# rgbstripe_msgeq7_pcb.net
KiCad netlist of a schematic drawn in EAGLE
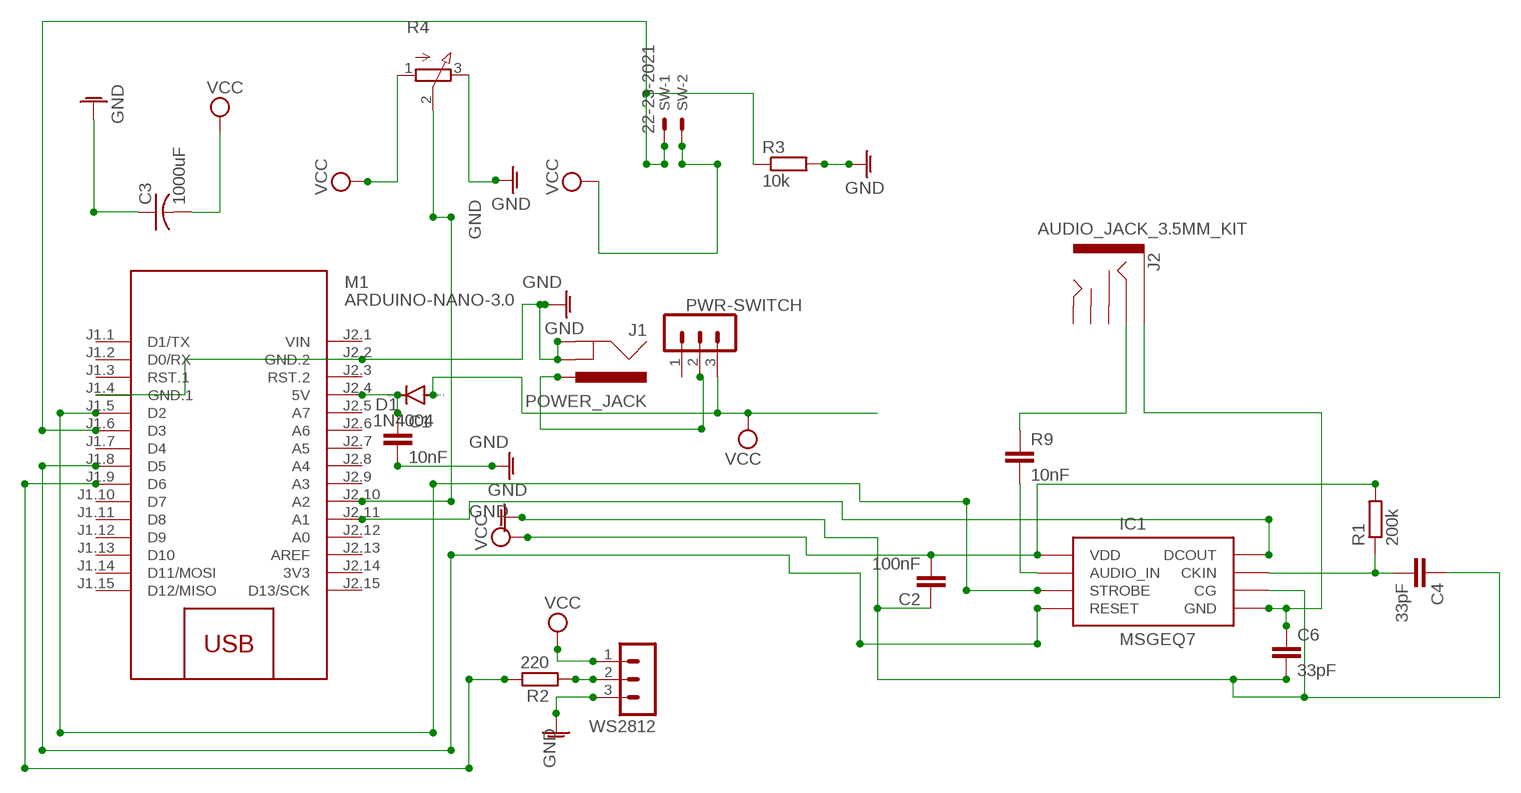
[diagram p0: schematic, sheet 1]

(export (version "E")
  (design (tool "Eeschema 10.0.6"))
  (components
    (comp (ref "C1")
      (value "10nF")
      (footprint "eagle-import:C025-025X050")
      (libsource (lib "eagle-import") (part "C-EU025-025X050"))
    )
    (comp (ref "C2")
      (value "100nF")
      (footprint "eagle-import:C025-025X050")
      (libsource (lib "eagle-import") (part "C-EU025-025X050"))
    )
    (comp (ref "C3")
      (value "1000uF")
      (footprint "eagle-import:C050-024X044")
      (libsource (lib "eagle-import") (part "C-US050-024X044"))
    )
    (comp (ref "C4")
      (value "33pF")
      (footprint "eagle-import:C025-025X050")
      (libsource (lib "eagle-import") (part "C-EU025-025X050"))
    )
    (comp (ref "C6")
      (value "33pF")
      (footprint "eagle-import:C025-025X050")
      (libsource (lib "eagle-import") (part "C-EU025-025X050"))
    )
    (comp (ref "D1")
      (value "1N4004")
      (footprint "eagle-import:DO41-10")
      (libsource (lib "eagle-import") (part "1N4004"))
    )
    (comp (ref "IC1")
      (value "MSGEQ7P")
      (footprint "eagle-import:DIP08")
      (libsource (lib "eagle-import") (part "MSGEQ7DIL"))
    )
    (comp (ref "J1")
      (value "POWER_JACK")
      (footprint "eagle-import:POWER_JACK_PTH")
      (libsource (lib "eagle-import") (part "POWER_JACK"))
    )
    (comp (ref "J2")
      (value "AUDIO_JACK_3.5MM_KIT")
      (footprint "eagle-import:AUDIO-JACK-KIT")
      (libsource (lib "eagle-import") (part "AUDIO_JACK_3.5MM_KIT"))
    )
    (comp (ref "M1")
      (value "ARDUINO-NANO-3.0")
      (footprint "eagle-import:ARDUINO-NANO-3.0")
      (libsource (lib "eagle-import") (part "ARDUINO-NANO-3.0"))
    )
    (comp (ref "PWR-SWITCH")
      (value "MA03-1")
      (footprint "eagle-import:MA03-1")
      (libsource (lib "eagle-import") (part "MA03-1"))
    )
    (comp (ref "R1")
      (value "200k")
      (footprint "eagle-import:0204_5")
      (libsource (lib "eagle-import") (part "R-EU_0204/5"))
    )
    (comp (ref "R2")
      (value "220")
      (footprint "eagle-import:0204_5")
      (libsource (lib "eagle-import") (part "R-EU_0204/5"))
    )
    (comp (ref "R3")
      (value "10k")
      (footprint "eagle-import:0204_5")
      (libsource (lib "eagle-import") (part "R-EU_0204/5"))
    )
    (comp (ref "R4")
      (value "3RP/1610N")
      (footprint "eagle-import:3RP_1610N")
      (libsource (lib "eagle-import") (part "3RP/1610N"))
    )
    (comp (ref "R9")
      (value "10nF")
      (footprint "eagle-import:C025-025X050")
      (libsource (lib "eagle-import") (part "C-EU025-025X050"))
    )
    (comp (ref "SW")
      (value "22-23-2021")
      (footprint "eagle-import:22-23-2021")
      (fields (field (name "MF") "MOLEX"))
      (libsource (lib "eagle-import") (part "22-23-2021"))
    )
    (comp (ref "WS2812")
      (value "MA03-1")
      (footprint "eagle-import:MA03-1")
      (libsource (lib "eagle-import") (part "MA03-1"))
    )
  )
  (nets
    (net (code "1") (name "/3V3") (class "Default")
      (node (ref "M1") (pin "J2.14") (pinfunction "3V3_J2.14") (pintype "power_in"))
    )
    (net (code "2") (name "/VIN") (class "Default")
      (node (ref "M1") (pin "J2.1") (pinfunction "VIN_J2.1") (pintype "power_in"))
    )
    (net (code "3") (name "GND") (class "Default")
      (node (ref "C1") (pin "2") (pinfunction "2_2") (pintype "passive"))
      (node (ref "C2") (pin "1") (pinfunction "1_1") (pintype "passive"))
      (node (ref "C3") (pin "1") (pinfunction "1_1") (pintype "passive"))
      (node (ref "C4") (pin "1") (pinfunction "1_1") (pintype "passive"))
      (node (ref "C6") (pin "2") (pinfunction "2_2") (pintype "passive"))
      (node (ref "IC1") (pin "6") (pinfunction "CG_6") (pintype "bidirectional"))
      (node (ref "J1") (pin "GND") (pinfunction "GND_GND") (pintype "bidirectional"))
      (node (ref "J1") (pin "GNDBREAK") (pinfunction "GNDBREAK_GNDBREAK") (pintype "bidirectional"))
      (node (ref "M1") (pin "J1.4") (pinfunction "GND.1_J1.4") (pintype "power_in"))
      (node (ref "M1") (pin "J2.2") (pinfunction "GND.2_J2.2") (pintype "power_in"))
      (node (ref "R3") (pin "2") (pinfunction "2_2") (pintype "passive"))
      (node (ref "R4") (pin "3") (pinfunction "E_3") (pintype "passive"))
      (node (ref "WS2812") (pin "3") (pinfunction "3_3") (pintype "passive"))
    )
    (net (code "4") (name "Net-(IC1-AUDIO_IN)") (class "Default")
      (node (ref "IC1") (pin "5") (pinfunction "AUDIO_IN_5") (pintype "input"))
      (node (ref "R9") (pin "2") (pinfunction "2_2") (pintype "passive"))
    )
    (net (code "5") (name "Net-(IC1-CKIN)") (class "Default")
      (node (ref "C4") (pin "2") (pinfunction "2_2") (pintype "passive"))
      (node (ref "IC1") (pin "8") (pinfunction "CKIN_8") (pintype "bidirectional"))
      (node (ref "R1") (pin "1") (pinfunction "1_1") (pintype "passive"))
    )
    (net (code "6") (name "Net-(IC1-DCOUT)") (class "Default")
      (node (ref "IC1") (pin "3") (pinfunction "DCOUT_3") (pintype "bidirectional"))
      (node (ref "M1") (pin "J2.11") (pinfunction "A1_J2.11") (pintype "bidirectional"))
    )
    (net (code "7") (name "Net-(IC1-GND)") (class "Default")
      (node (ref "C6") (pin "1") (pinfunction "1_1") (pintype "passive"))
      (node (ref "IC1") (pin "2") (pinfunction "GND_2") (pintype "bidirectional"))
      (node (ref "J2") (pin "SLEEVE") (pinfunction "SLEEVE_SLEEVE") (pintype "bidirectional"))
    )
    (net (code "8") (name "Net-(IC1-RESET)") (class "Default")
      (node (ref "IC1") (pin "7") (pinfunction "RESET_7") (pintype "input"))
      (node (ref "M1") (pin "J1.8") (pinfunction "D5_J1.8") (pintype "bidirectional"))
    )
    (net (code "9") (name "Net-(IC1-STROBE)") (class "Default")
      (node (ref "IC1") (pin "4") (pinfunction "STROBE_4") (pintype "input"))
      (node (ref "M1") (pin "J1.5") (pinfunction "D2_J1.5") (pintype "bidirectional"))
    )
    (net (code "10") (name "Net-(J1-PadPWR)") (class "Default")
      (node (ref "J1") (pin "PWR") (pinfunction "PWR_PWR") (pintype "bidirectional"))
      (node (ref "PWR-SWITCH") (pin "2") (pinfunction "2_2") (pintype "passive"))
    )
    (net (code "11") (name "Net-(J2-PadRING)") (class "Default")
      (node (ref "J2") (pin "RING") (pinfunction "RING_RING") (pintype "bidirectional"))
      (node (ref "R9") (pin "1") (pinfunction "1_1") (pintype "passive"))
    )
    (net (code "12") (name "Net-(M1-5V)") (class "Default")
      (node (ref "C1") (pin "1") (pinfunction "1_1") (pintype "passive"))
      (node (ref "D1") (pin "C") (pinfunction "C_C") (pintype "passive"))
      (node (ref "M1") (pin "J2.4") (pinfunction "5V_J2.4") (pintype "power_in"))
    )
    (net (code "13") (name "Net-(M1-A2)") (class "Default")
      (node (ref "M1") (pin "J2.10") (pinfunction "A2_J2.10") (pintype "bidirectional"))
      (node (ref "R4") (pin "2") (pinfunction "S_2") (pintype "passive"))
    )
    (net (code "14") (name "Net-(M1-D3)") (class "Default")
      (node (ref "M1") (pin "J1.6") (pinfunction "D3_J1.6") (pintype "bidirectional"))
      (node (ref "R3") (pin "1") (pinfunction "1_1") (pintype "passive"))
      (node (ref "SW") (pin "1") (pinfunction "S_1") (pintype "passive"))
    )
    (net (code "15") (name "Net-(M1-D6)") (class "Default")
      (node (ref "M1") (pin "J1.9") (pinfunction "D6_J1.9") (pintype "bidirectional"))
      (node (ref "R2") (pin "2") (pinfunction "2_2") (pintype "passive"))
    )
    (net (code "16") (name "Net-(R2-Pad1)") (class "Default")
      (node (ref "R2") (pin "1") (pinfunction "1_1") (pintype "passive"))
      (node (ref "WS2812") (pin "2") (pinfunction "2_2") (pintype "passive"))
    )
    (net (code "17") (name "VCC") (class "Default")
      (node (ref "C2") (pin "2") (pinfunction "2_2") (pintype "passive"))
      (node (ref "C3") (pin "2") (pinfunction "2_2") (pintype "passive"))
      (node (ref "D1") (pin "A") (pinfunction "A_A") (pintype "passive"))
      (node (ref "IC1") (pin "1") (pinfunction "VDD_1") (pintype "input"))
      (node (ref "PWR-SWITCH") (pin "3") (pinfunction "3_3") (pintype "passive"))
      (node (ref "R1") (pin "2") (pinfunction "2_2") (pintype "passive"))
      (node (ref "R4") (pin "1") (pinfunction "A_1") (pintype "passive"))
      (node (ref "SW") (pin "2") (pinfunction "S_2") (pintype "passive"))
      (node (ref "WS2812") (pin "1") (pinfunction "1_1") (pintype "passive"))
    )
    (net (code "18") (name "unconnected-(J2-PadRSH)") (class "Default")
      (node (ref "J2") (pin "RSH") (pinfunction "RSH_RSH") (pintype "bidirectional"))
    )
    (net (code "19") (name "unconnected-(J2-PadTIP)") (class "Default")
      (node (ref "J2") (pin "TIP") (pinfunction "TIP_TIP") (pintype "bidirectional"))
    )
    (net (code "20") (name "unconnected-(J2-PadTSH)") (class "Default")
      (node (ref "J2") (pin "TSH") (pinfunction "TSH_TSH") (pintype "bidirectional"))
    )
    (net (code "21") (name "unconnected-(M1-A0-PadJ2.12)") (class "Default")
      (node (ref "M1") (pin "J2.12") (pinfunction "A0_J2.12") (pintype "bidirectional"))
    )
    (net (code "22") (name "unconnected-(M1-A3-PadJ2.9)") (class "Default")
      (node (ref "M1") (pin "J2.9") (pinfunction "A3_J2.9") (pintype "bidirectional"))
    )
    (net (code "23") (name "unconnected-(M1-A4-PadJ2.8)") (class "Default")
      (node (ref "M1") (pin "J2.8") (pinfunction "A4_J2.8") (pintype "bidirectional"))
    )
    (net (code "24") (name "unconnected-(M1-A5-PadJ2.7)") (class "Default")
      (node (ref "M1") (pin "J2.7") (pinfunction "A5_J2.7") (pintype "bidirectional"))
    )
    (net (code "25") (name "unconnected-(M1-A6-PadJ2.6)") (class "Default")
      (node (ref "M1") (pin "J2.6") (pinfunction "A6_J2.6") (pintype "bidirectional"))
    )
    (net (code "26") (name "unconnected-(M1-A7-PadJ2.5)") (class "Default")
      (node (ref "M1") (pin "J2.5") (pinfunction "A7_J2.5") (pintype "bidirectional"))
    )
    (net (code "27") (name "unconnected-(M1-AREF-PadJ2.13)") (class "Default")
      (node (ref "M1") (pin "J2.13") (pinfunction "AREF_J2.13") (pintype "bidirectional"))
    )
    (net (code "28") (name "unconnected-(M1-D0{slash}RX-PadJ1.2)") (class "Default")
      (node (ref "M1") (pin "J1.2") (pinfunction "D0/RX_J1.2") (pintype "bidirectional"))
    )
    (net (code "29") (name "unconnected-(M1-D1{slash}TX-PadJ1.1)") (class "Default")
      (node (ref "M1") (pin "J1.1") (pinfunction "D1/TX_J1.1") (pintype "bidirectional"))
    )
    (net (code "30") (name "unconnected-(M1-D4-PadJ1.7)") (class "Default")
      (node (ref "M1") (pin "J1.7") (pinfunction "D4_J1.7") (pintype "bidirectional"))
    )
    (net (code "31") (name "unconnected-(M1-D7-PadJ1.10)") (class "Default")
      (node (ref "M1") (pin "J1.10") (pinfunction "D7_J1.10") (pintype "bidirectional"))
    )
    (net (code "32") (name "unconnected-(M1-D8-PadJ1.11)") (class "Default")
      (node (ref "M1") (pin "J1.11") (pinfunction "D8_J1.11") (pintype "bidirectional"))
    )
    (net (code "33") (name "unconnected-(M1-D9-PadJ1.12)") (class "Default")
      (node (ref "M1") (pin "J1.12") (pinfunction "D9_J1.12") (pintype "bidirectional"))
    )
    (net (code "34") (name "unconnected-(M1-D10-PadJ1.13)") (class "Default")
      (node (ref "M1") (pin "J1.13") (pinfunction "D10_J1.13") (pintype "bidirectional"))
    )
    (net (code "35") (name "unconnected-(M1-D11{slash}MOSI-PadJ1.14)") (class "Default")
      (node (ref "M1") (pin "J1.14") (pinfunction "D11/MOSI_J1.14") (pintype "bidirectional"))
    )
    (net (code "36") (name "unconnected-(M1-D12{slash}MISO-PadJ1.15)") (class "Default")
      (node (ref "M1") (pin "J1.15") (pinfunction "D12/MISO_J1.15") (pintype "bidirectional"))
    )
    (net (code "37") (name "unconnected-(M1-D13{slash}SCK-PadJ2.15)") (class "Default")
      (node (ref "M1") (pin "J2.15") (pinfunction "D13/SCK_J2.15") (pintype "bidirectional"))
    )
    (net (code "38") (name "unconnected-(M1-RST.1-PadJ1.3)") (class "Default")
      (node (ref "M1") (pin "J1.3") (pinfunction "RST.1_J1.3") (pintype "bidirectional"))
    )
    (net (code "39") (name "unconnected-(M1-RST.2-PadJ2.3)") (class "Default")
      (node (ref "M1") (pin "J2.3") (pinfunction "RST.2_J2.3") (pintype "bidirectional"))
    )
    (net (code "40") (name "unconnected-(PWR-SWITCH-Pad1)") (class "Default")
      (node (ref "PWR-SWITCH") (pin "1") (pinfunction "1_1") (pintype "passive"))
    )
  )
)
